# ProtoHu_rev_B_layer1.net
KiCad netlist of a schematic drawn in EAGLE
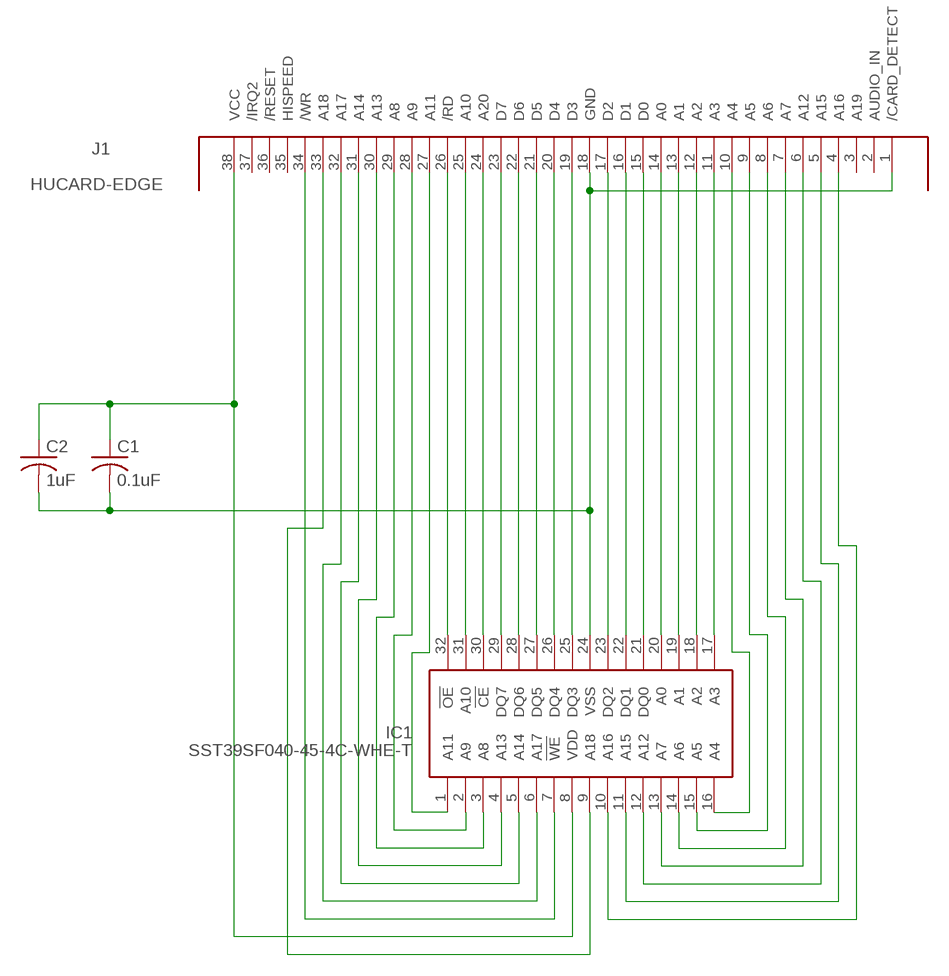
[diagram p0: schematic, sheet 1]

(export (version "E")
  (design (tool "Eeschema 10.0.6"))
  (components
    (comp (ref "C1")
      (value "0.1uF")
      (footprint "eagle-import:C0603")
      (libsource (lib "eagle-import") (part "C-USC0603"))
    )
    (comp (ref "C2")
      (value "1uF")
      (footprint "eagle-import:C0603")
      (libsource (lib "eagle-import") (part "C-USC0603"))
    )
    (comp (ref "IC1")
      (value "SST39SF040-45-4C-WHE-T")
      (footprint "eagle-import:SOP50P1400X120-32N")
      (fields (field (name "MOUSER_PART_NUMBER") "579-39SF0404CWHET"))
      (libsource (lib "eagle-import") (part "SST39SF040-45-4C-WHE-T"))
    )
    (comp (ref "J1")
      (value "HUCARD-EDGE")
      (footprint "eagle-import:HUCARD-EDGE")
      (libsource (lib "eagle-import") (part "HUCARD-EDGE"))
    )
  )
  (nets
    (net (code "1") (name "Net-(IC1-A0)") (class "Default")
      (node (ref "IC1") (pin "20") (pinfunction "A0_20") (pintype "input"))
      (node (ref "J1") (pin "14") (pinfunction "A0_14") (pintype "output"))
    )
    (net (code "2") (name "Net-(IC1-A1)") (class "Default")
      (node (ref "IC1") (pin "19") (pinfunction "A1_19") (pintype "input"))
      (node (ref "J1") (pin "13") (pinfunction "A1_13") (pintype "output"))
    )
    (net (code "3") (name "Net-(IC1-A2)") (class "Default")
      (node (ref "IC1") (pin "18") (pinfunction "A2_18") (pintype "input"))
      (node (ref "J1") (pin "12") (pinfunction "A2_12") (pintype "output"))
    )
    (net (code "4") (name "Net-(IC1-A3)") (class "Default")
      (node (ref "IC1") (pin "17") (pinfunction "A3_17") (pintype "input"))
      (node (ref "J1") (pin "11") (pinfunction "A3_11") (pintype "output"))
    )
    (net (code "5") (name "Net-(IC1-A4)") (class "Default")
      (node (ref "IC1") (pin "16") (pinfunction "A4_16") (pintype "input"))
      (node (ref "J1") (pin "10") (pinfunction "A4_10") (pintype "output"))
    )
    (net (code "6") (name "Net-(IC1-A5)") (class "Default")
      (node (ref "IC1") (pin "15") (pinfunction "A5_15") (pintype "input"))
      (node (ref "J1") (pin "9") (pinfunction "A5_9") (pintype "output"))
    )
    (net (code "7") (name "Net-(IC1-A6)") (class "Default")
      (node (ref "IC1") (pin "14") (pinfunction "A6_14") (pintype "input"))
      (node (ref "J1") (pin "8") (pinfunction "A6_8") (pintype "output"))
    )
    (net (code "8") (name "Net-(IC1-A7)") (class "Default")
      (node (ref "IC1") (pin "13") (pinfunction "A7_13") (pintype "input"))
      (node (ref "J1") (pin "7") (pinfunction "A7_7") (pintype "output"))
    )
    (net (code "9") (name "Net-(IC1-A8)") (class "Default")
      (node (ref "IC1") (pin "3") (pinfunction "A8_3") (pintype "input"))
      (node (ref "J1") (pin "29") (pinfunction "A8_29") (pintype "output"))
    )
    (net (code "10") (name "Net-(IC1-A9)") (class "Default")
      (node (ref "IC1") (pin "2") (pinfunction "A9_2") (pintype "input"))
      (node (ref "J1") (pin "28") (pinfunction "A9_28") (pintype "output"))
    )
    (net (code "11") (name "Net-(IC1-A10)") (class "Default")
      (node (ref "IC1") (pin "31") (pinfunction "A10_31") (pintype "input"))
      (node (ref "J1") (pin "25") (pinfunction "A10_25") (pintype "output"))
    )
    (net (code "12") (name "Net-(IC1-A11)") (class "Default")
      (node (ref "IC1") (pin "1") (pinfunction "A11_1") (pintype "input"))
      (node (ref "J1") (pin "27") (pinfunction "A11_27") (pintype "output"))
    )
    (net (code "13") (name "Net-(IC1-A12)") (class "Default")
      (node (ref "IC1") (pin "12") (pinfunction "A12_12") (pintype "input"))
      (node (ref "J1") (pin "6") (pinfunction "A12_6") (pintype "output"))
    )
    (net (code "14") (name "Net-(IC1-A13)") (class "Default")
      (node (ref "IC1") (pin "4") (pinfunction "A13_4") (pintype "input"))
      (node (ref "J1") (pin "30") (pinfunction "A13_30") (pintype "output"))
    )
    (net (code "15") (name "Net-(IC1-A14)") (class "Default")
      (node (ref "IC1") (pin "5") (pinfunction "A14_5") (pintype "input"))
      (node (ref "J1") (pin "31") (pinfunction "A14_31") (pintype "output"))
    )
    (net (code "16") (name "Net-(IC1-A15)") (class "Default")
      (node (ref "IC1") (pin "11") (pinfunction "A15_11") (pintype "input"))
      (node (ref "J1") (pin "5") (pinfunction "A15_5") (pintype "output"))
    )
    (net (code "17") (name "Net-(IC1-A16)") (class "Default")
      (node (ref "IC1") (pin "10") (pinfunction "A16_10") (pintype "input"))
      (node (ref "J1") (pin "4") (pinfunction "A16_4") (pintype "output"))
    )
    (net (code "18") (name "Net-(IC1-A17)") (class "Default")
      (node (ref "IC1") (pin "6") (pinfunction "A17_6") (pintype "input"))
      (node (ref "J1") (pin "32") (pinfunction "A17_32") (pintype "output"))
    )
    (net (code "19") (name "Net-(IC1-A18)") (class "Default")
      (node (ref "IC1") (pin "9") (pinfunction "A18_9") (pintype "input"))
      (node (ref "J1") (pin "33") (pinfunction "A18_33") (pintype "output"))
    )
    (net (code "20") (name "Net-(IC1-DQ0)") (class "Default")
      (node (ref "IC1") (pin "21") (pinfunction "DQ0_21") (pintype "bidirectional"))
      (node (ref "J1") (pin "15") (pinfunction "D0_15") (pintype "bidirectional"))
    )
    (net (code "21") (name "Net-(IC1-DQ1)") (class "Default")
      (node (ref "IC1") (pin "22") (pinfunction "DQ1_22") (pintype "bidirectional"))
      (node (ref "J1") (pin "16") (pinfunction "D1_16") (pintype "bidirectional"))
    )
    (net (code "22") (name "Net-(IC1-DQ2)") (class "Default")
      (node (ref "IC1") (pin "23") (pinfunction "DQ2_23") (pintype "bidirectional"))
      (node (ref "J1") (pin "17") (pinfunction "D2_17") (pintype "bidirectional"))
    )
    (net (code "23") (name "Net-(IC1-DQ3)") (class "Default")
      (node (ref "IC1") (pin "25") (pinfunction "DQ3_25") (pintype "bidirectional"))
      (node (ref "J1") (pin "19") (pinfunction "D3_19") (pintype "bidirectional"))
    )
    (net (code "24") (name "Net-(IC1-DQ4)") (class "Default")
      (node (ref "IC1") (pin "26") (pinfunction "DQ4_26") (pintype "bidirectional"))
      (node (ref "J1") (pin "20") (pinfunction "D4_20") (pintype "bidirectional"))
    )
    (net (code "25") (name "Net-(IC1-DQ5)") (class "Default")
      (node (ref "IC1") (pin "27") (pinfunction "DQ5_27") (pintype "bidirectional"))
      (node (ref "J1") (pin "21") (pinfunction "D5_21") (pintype "bidirectional"))
    )
    (net (code "26") (name "Net-(IC1-DQ6)") (class "Default")
      (node (ref "IC1") (pin "28") (pinfunction "DQ6_28") (pintype "bidirectional"))
      (node (ref "J1") (pin "22") (pinfunction "D6_22") (pintype "bidirectional"))
    )
    (net (code "27") (name "Net-(IC1-DQ7)") (class "Default")
      (node (ref "IC1") (pin "29") (pinfunction "DQ7_29") (pintype "bidirectional"))
      (node (ref "J1") (pin "23") (pinfunction "D7_23") (pintype "bidirectional"))
    )
    (net (code "28") (name "Net-(IC1-VDD)") (class "Default")
      (node (ref "C1") (pin "1") (pinfunction "1_1") (pintype "passive"))
      (node (ref "C2") (pin "1") (pinfunction "1_1") (pintype "passive"))
      (node (ref "IC1") (pin "8") (pinfunction "VDD_8") (pintype "power_in"))
      (node (ref "J1") (pin "38") (pinfunction "VCC_38") (pintype "power_in"))
    )
    (net (code "29") (name "Net-(IC1-VSS)") (class "Default")
      (node (ref "C1") (pin "2") (pinfunction "2_2") (pintype "passive"))
      (node (ref "C2") (pin "2") (pinfunction "2_2") (pintype "passive"))
      (node (ref "IC1") (pin "24") (pinfunction "VSS_24") (pintype "power_in"))
      (node (ref "J1") (pin "1") (pinfunction "/CARD_DETECT_1") (pintype "input"))
      (node (ref "J1") (pin "18") (pinfunction "GND_18") (pintype "power_in"))
    )
    (net (code "30") (name "Net-(IC1-~{CE})") (class "Default")
      (node (ref "IC1") (pin "30") (pinfunction "~{CE}_30") (pintype "input"))
      (node (ref "J1") (pin "24") (pinfunction "A20_24") (pintype "output"))
    )
    (net (code "31") (name "Net-(IC1-~{OE})") (class "Default")
      (node (ref "IC1") (pin "32") (pinfunction "~{OE}_32") (pintype "input"))
      (node (ref "J1") (pin "26") (pinfunction "/RD_26") (pintype "output"))
    )
    (net (code "32") (name "Net-(IC1-~{WE})") (class "Default")
      (node (ref "IC1") (pin "7") (pinfunction "~{WE}_7") (pintype "input"))
      (node (ref "J1") (pin "34") (pinfunction "/WR_34") (pintype "output"))
    )
    (net (code "33") (name "unconnected-(J1-A19-Pad3)") (class "Default")
      (node (ref "J1") (pin "3") (pinfunction "A19_3") (pintype "output"))
    )
    (net (code "34") (name "unconnected-(J1-AUDIO_IN-Pad2)") (class "Default")
      (node (ref "J1") (pin "2") (pinfunction "AUDIO_IN_2") (pintype "input"))
    )
    (net (code "35") (name "unconnected-(J1-HISPEED-Pad35)") (class "Default")
      (node (ref "J1") (pin "35") (pinfunction "HISPEED_35") (pintype "output"))
    )
    (net (code "36") (name "unconnected-(J1-{slash}IRQ2-Pad37)") (class "Default")
      (node (ref "J1") (pin "37") (pinfunction "/IRQ2_37") (pintype "bidirectional"))
    )
    (net (code "37") (name "unconnected-(J1-{slash}RESET-Pad36)") (class "Default")
      (node (ref "J1") (pin "36") (pinfunction "/RESET_36") (pintype "bidirectional"))
    )
  )
)
